# AMP.net
KiCad netlist of a schematic drawn in Altium Designer
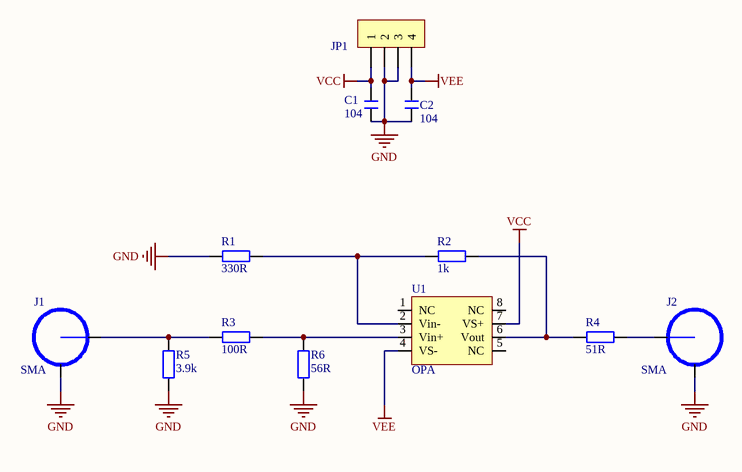
[diagram p0: AMP.SchDoc]

(export (version "E")
  (design (tool "Eeschema 10.0.6"))
  (components
    (comp (ref "C1")
      (value "104")
      (footprint "C 0805_L")
      (description "无极性贴片电容")
      (fields (field (name "版权归属") "源创客"))
      (libsource (lib "3.1   - 电阻-电容-电感") (part "C"))
    )
    (comp (ref "C2")
      (value "104")
      (footprint "C 0805_L")
      (description "无极性贴片电容")
      (fields (field (name "版权归属") "源创客"))
      (libsource (lib "3.1   - 电阻-电容-电感") (part "C"))
    )
    (comp (ref "J1") (value "SMA") (footprint "HDR2.54-LI-2P") (libsource (lib "电子竞赛") (part "SMA")))
    (comp (ref "J2") (value "SMA") (footprint "HDR2.54-LI-2P") (libsource (lib "") (part "SMA_1")))
    (comp (ref "JP1")
      (value "HDR-1X4")
      (footprint "KF2510-LI-4P")
      (description "4P接插件")
      (fields (field (name "版权归属") "源创客"))
      (libsource (lib "4.5   - 接插件-脚距2.54") (part "Header 4"))
    )
    (comp (ref "R1")
      (value "330R")
      (footprint "R 0805_L")
      (description "贴片电阻")
      (fields (field (name "版权归属") "源创客"))
      (libsource (lib "3.1   - 电阻-电容-电感") (part "R"))
    )
    (comp (ref "R2")
      (value "1k")
      (footprint "R 0805_L")
      (description "贴片电阻")
      (fields (field (name "版权归属") "源创客"))
      (libsource (lib "3.1   - 电阻-电容-电感") (part "R"))
    )
    (comp (ref "R3")
      (value "100R")
      (footprint "R 0805_L")
      (description "贴片电阻")
      (fields (field (name "版权归属") "源创客"))
      (libsource (lib "3.1   - 电阻-电容-电感") (part "R"))
    )
    (comp (ref "R4")
      (value "51R")
      (footprint "R 0805_L")
      (description "贴片电阻")
      (fields (field (name "版权归属") "源创客"))
      (libsource (lib "3.1   - 电阻-电容-电感") (part "R"))
    )
    (comp (ref "R5")
      (value "3.9k")
      (footprint "R 0805_L")
      (description "贴片电阻")
      (fields (field (name "版权归属") "源创客"))
      (libsource (lib "3.1   - 电阻-电容-电感") (part "R"))
    )
    (comp (ref "R6")
      (value "56R")
      (footprint "R 0805_L")
      (description "贴片电阻")
      (fields (field (name "版权归属") "源创客"))
      (libsource (lib "3.1   - 电阻-电容-电感") (part "R"))
    )
    (comp (ref "U1") (value "OPA") (footprint "SOP8_M") (libsource (lib "电子竞赛") (part "单运放")))
  )
  (nets
    (net (code "1") (name "GND") (class "Default")
      (node (ref "C1") (pin "1") (pinfunction "1_1") (pintype "passive"))
      (node (ref "C2") (pin "1") (pinfunction "1_1") (pintype "passive"))
      (node (ref "J1") (pin "2") (pinfunction "2_2") (pintype "passive"))
      (node (ref "J2") (pin "2") (pinfunction "2_2") (pintype "passive"))
      (node (ref "JP1") (pin "2") (pinfunction "2_2") (pintype "passive"))
      (node (ref "JP1") (pin "3") (pinfunction "3_3") (pintype "passive"))
      (node (ref "R1") (pin "1") (pinfunction "1_1") (pintype "passive"))
      (node (ref "R5") (pin "1") (pinfunction "1_1") (pintype "passive"))
      (node (ref "R6") (pin "1") (pinfunction "1_1") (pintype "passive"))
    )
    (net (code "2") (name "Net-(J1-Pad1)") (class "Default")
      (node (ref "J1") (pin "1") (pinfunction "1_1") (pintype "passive"))
      (node (ref "R3") (pin "1") (pinfunction "1_1") (pintype "passive"))
      (node (ref "R5") (pin "2") (pinfunction "2_2") (pintype "passive"))
    )
    (net (code "3") (name "Net-(J2-Pad1)") (class "Default")
      (node (ref "J2") (pin "1") (pinfunction "1_1") (pintype "passive"))
      (node (ref "R4") (pin "2") (pinfunction "2_2") (pintype "passive"))
    )
    (net (code "4") (name "Net-(U1-Vin+)") (class "Default")
      (node (ref "R3") (pin "2") (pinfunction "2_2") (pintype "passive"))
      (node (ref "R6") (pin "2") (pinfunction "2_2") (pintype "passive"))
      (node (ref "U1") (pin "3") (pinfunction "Vin+_3") (pintype "passive"))
    )
    (net (code "5") (name "Net-(U1-Vin-)") (class "Default")
      (node (ref "R1") (pin "2") (pinfunction "2_2") (pintype "passive"))
      (node (ref "R2") (pin "1") (pinfunction "1_1") (pintype "passive"))
      (node (ref "U1") (pin "2") (pinfunction "Vin-_2") (pintype "passive"))
    )
    (net (code "6") (name "Net-(U1-Vout)") (class "Default")
      (node (ref "R2") (pin "2") (pinfunction "2_2") (pintype "passive"))
      (node (ref "R4") (pin "1") (pinfunction "1_1") (pintype "passive"))
      (node (ref "U1") (pin "6") (pinfunction "Vout_6") (pintype "passive"))
    )
    (net (code "7") (name "VCC") (class "Default")
      (node (ref "C1") (pin "2") (pinfunction "2_2") (pintype "passive"))
      (node (ref "JP1") (pin "1") (pinfunction "1_1") (pintype "passive"))
      (node (ref "U1") (pin "7") (pinfunction "VS+_7") (pintype "passive"))
    )
    (net (code "8") (name "VEE") (class "Default")
      (node (ref "C2") (pin "2") (pinfunction "2_2") (pintype "passive"))
      (node (ref "JP1") (pin "4") (pinfunction "4_4") (pintype "passive"))
      (node (ref "U1") (pin "4") (pinfunction "VS-_4") (pintype "passive"))
    )
    (net (code "9") (name "unconnected-(U1-NC-Pad1)") (class "Default")
      (node (ref "U1") (pin "1") (pinfunction "NC_1") (pintype "passive"))
    )
    (net (code "10") (name "unconnected-(U1-NC-Pad5)") (class "Default")
      (node (ref "U1") (pin "5") (pinfunction "NC_5") (pintype "passive"))
    )
    (net (code "11") (name "unconnected-(U1-NC-Pad8)") (class "Default")
      (node (ref "U1") (pin "8") (pinfunction "NC_8") (pintype "passive"))
    )
  )
)
